# VCCS_Unit.net
KiCad netlist of a schematic drawn in EAGLE
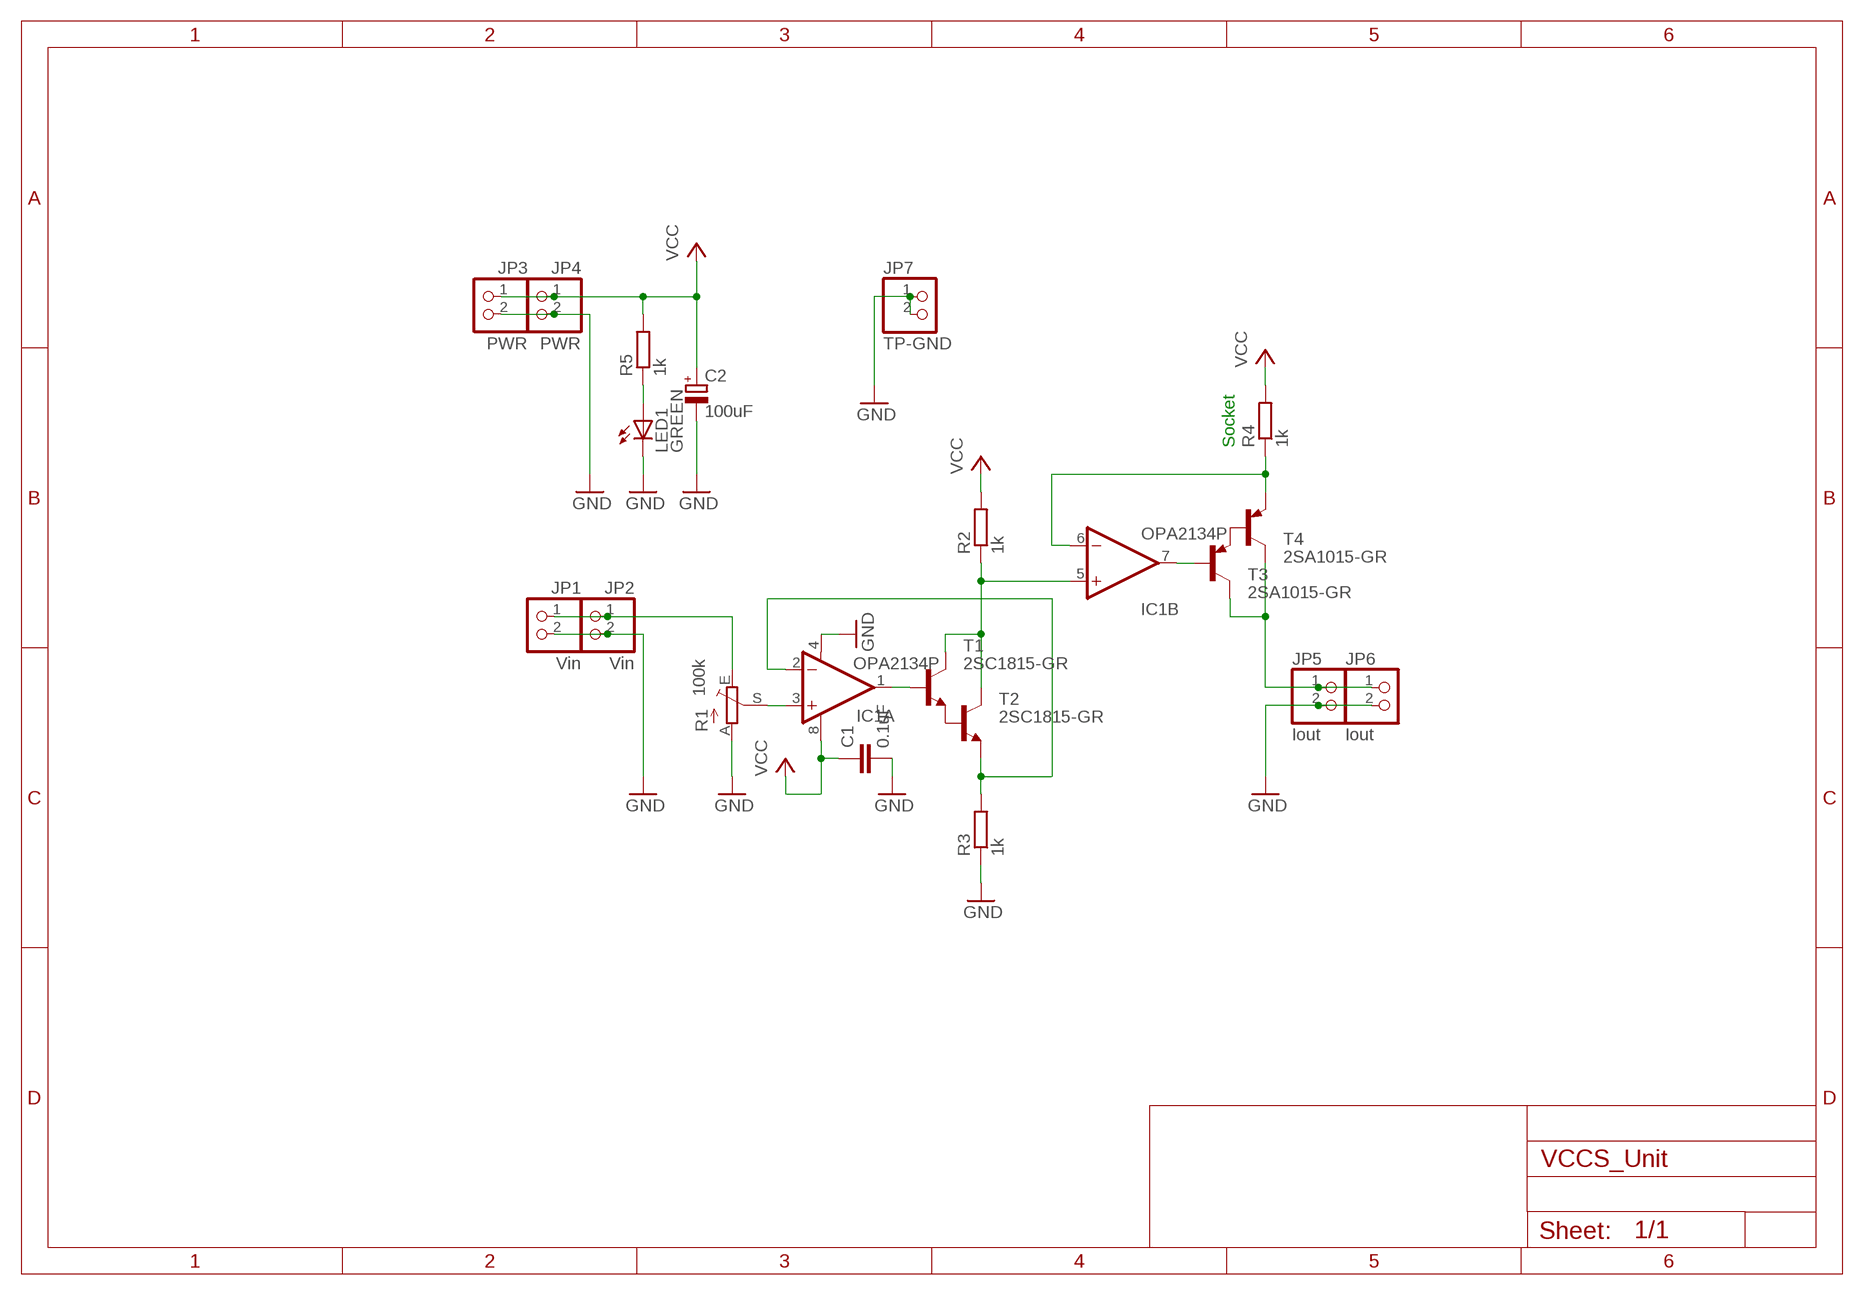
[diagram p0: schematic, sheet 1]

(export (version "E")
  (design (tool "Eeschema 10.0.6"))
  (components
    (comp (ref "C1")
      (value "0.1uF")
      (footprint "eagle-import:C025-024X044")
      (libsource (lib "eagle-import") (part "C-EU025-024X044"))
    )
    (comp (ref "C2")
      (value "100uF")
      (footprint "eagle-import:E2,5-7")
      (libsource (lib "eagle-import") (part "CPOL-EUE2.5-7"))
    )
    (comp (ref "IC1")
      (value "OPA2134P")
      (footprint "eagle-import:DIL08")
      (fields (field (name "MF") "TEXAS INSTRUMENTS") (field (name "MPN") "OPA2134PA"))
      (libsource (lib "eagle-import") (part "OPA2134P"))
    )
    (comp (ref "JP1")
      (value "Vin")
      (footprint "eagle-import:1X02")
      (libsource (lib "eagle-import") (part "PINHD-1X2"))
    )
    (comp (ref "JP2")
      (value "Vin")
      (footprint "eagle-import:1X02")
      (libsource (lib "eagle-import") (part "PINHD-1X2"))
    )
    (comp (ref "JP3")
      (value "PWR")
      (footprint "eagle-import:1X02")
      (libsource (lib "eagle-import") (part "PINHD-1X2"))
    )
    (comp (ref "JP4")
      (value "PWR")
      (footprint "eagle-import:1X02")
      (libsource (lib "eagle-import") (part "PINHD-1X2"))
    )
    (comp (ref "JP5")
      (value "Iout")
      (footprint "eagle-import:1X02")
      (libsource (lib "eagle-import") (part "PINHD-1X2"))
    )
    (comp (ref "JP6")
      (value "Iout")
      (footprint "eagle-import:1X02")
      (libsource (lib "eagle-import") (part "PINHD-1X2"))
    )
    (comp (ref "JP7")
      (value "TP-GND")
      (footprint "eagle-import:1X02")
      (libsource (lib "eagle-import") (part "PINHD-1X2"))
    )
    (comp (ref "LED1")
      (value "GREEN")
      (footprint "eagle-import:LED3MM")
      (libsource (lib "eagle-import") (part "LED3MM"))
    )
    (comp (ref "R1")
      (value "100k")
      (footprint "eagle-import:B25P")
      (libsource (lib "eagle-import") (part "TRIM_EU-B25P"))
    )
    (comp (ref "R2")
      (value "1k")
      (footprint "eagle-import:0207_7")
      (libsource (lib "eagle-import") (part "R-EU_0207/7"))
    )
    (comp (ref "R3")
      (value "1k")
      (footprint "eagle-import:0207_7")
      (libsource (lib "eagle-import") (part "R-EU_0207/7"))
    )
    (comp (ref "R4")
      (value "1k")
      (footprint "eagle-import:0207_7")
      (libsource (lib "eagle-import") (part "R-EU_0207/7"))
    )
    (comp (ref "R5")
      (value "1k")
      (footprint "eagle-import:0207_7")
      (libsource (lib "eagle-import") (part "R-EU_0207/7"))
    )
    (comp (ref "T1")
      (value "2SC1815-GR")
      (footprint "eagle-import:TO92-ECB")
      (libsource (lib "eagle-import") (part "-NPN-TO92-ECB"))
    )
    (comp (ref "T2")
      (value "2SC1815-GR")
      (footprint "eagle-import:TO92-ECB")
      (libsource (lib "eagle-import") (part "-NPN-TO92-ECB"))
    )
    (comp (ref "T3")
      (value "2SA1015-GR")
      (footprint "eagle-import:TO92-ECB")
      (libsource (lib "eagle-import") (part "-PNP-TO92-ECB"))
    )
    (comp (ref "T4")
      (value "2SA1015-GR")
      (footprint "eagle-import:TO92-ECB")
      (libsource (lib "eagle-import") (part "-PNP-TO92-ECB"))
    )
  )
  (nets
    (net (code "1") (name "GND") (class "Default")
      (node (ref "C1") (pin "2") (pinfunction "2_2") (pintype "passive"))
      (node (ref "C2") (pin "-") (pinfunction "-_-") (pintype "passive"))
      (node (ref "IC1") (pin "4") (pinfunction "V-_4") (pintype "power_in"))
      (node (ref "JP1") (pin "2") (pinfunction "2_2") (pintype "passive"))
      (node (ref "JP2") (pin "2") (pinfunction "2_2") (pintype "passive"))
      (node (ref "JP3") (pin "2") (pinfunction "2_2") (pintype "passive"))
      (node (ref "JP4") (pin "2") (pinfunction "2_2") (pintype "passive"))
      (node (ref "JP5") (pin "2") (pinfunction "2_2") (pintype "passive"))
      (node (ref "JP6") (pin "2") (pinfunction "2_2") (pintype "passive"))
      (node (ref "JP7") (pin "1") (pinfunction "1_1") (pintype "passive"))
      (node (ref "JP7") (pin "2") (pinfunction "2_2") (pintype "passive"))
      (node (ref "LED1") (pin "K") (pinfunction "C_K") (pintype "passive"))
      (node (ref "R1") (pin "A") (pinfunction "A_A") (pintype "passive"))
      (node (ref "R3") (pin "1") (pinfunction "1_1") (pintype "passive"))
    )
    (net (code "2") (name "Net-(IC1A-+IN)") (class "Default")
      (node (ref "IC1") (pin "3") (pinfunction "+IN_3") (pintype "input"))
      (node (ref "R1") (pin "S") (pinfunction "S_S") (pintype "passive"))
    )
    (net (code "3") (name "Net-(IC1A--IN)") (class "Default")
      (node (ref "IC1") (pin "2") (pinfunction "-IN_2") (pintype "input"))
      (node (ref "R3") (pin "2") (pinfunction "2_2") (pintype "passive"))
      (node (ref "T2") (pin "E") (pinfunction "E_E") (pintype "passive"))
    )
    (net (code "4") (name "Net-(IC1A-OUT)") (class "Default")
      (node (ref "IC1") (pin "1") (pinfunction "OUT_1") (pintype "output"))
      (node (ref "T1") (pin "B") (pinfunction "B_B") (pintype "passive"))
    )
    (net (code "5") (name "Net-(IC1B-+IN)") (class "Default")
      (node (ref "IC1") (pin "5") (pinfunction "+IN_5") (pintype "input"))
      (node (ref "R2") (pin "1") (pinfunction "1_1") (pintype "passive"))
      (node (ref "T1") (pin "C") (pinfunction "C_C") (pintype "passive"))
      (node (ref "T2") (pin "C") (pinfunction "C_C") (pintype "passive"))
    )
    (net (code "6") (name "Net-(IC1B--IN)") (class "Default")
      (node (ref "IC1") (pin "6") (pinfunction "-IN_6") (pintype "input"))
      (node (ref "R4") (pin "1") (pinfunction "1_1") (pintype "passive"))
      (node (ref "T4") (pin "E") (pinfunction "E_E") (pintype "passive"))
    )
    (net (code "7") (name "Net-(IC1B-OUT)") (class "Default")
      (node (ref "IC1") (pin "7") (pinfunction "OUT_7") (pintype "output"))
      (node (ref "T3") (pin "B") (pinfunction "B_B") (pintype "passive"))
    )
    (net (code "8") (name "Net-(JP1-Pad1)") (class "Default")
      (node (ref "JP1") (pin "1") (pinfunction "1_1") (pintype "passive"))
      (node (ref "JP2") (pin "1") (pinfunction "1_1") (pintype "passive"))
      (node (ref "R1") (pin "E") (pinfunction "E_E") (pintype "passive"))
    )
    (net (code "9") (name "Net-(JP5-Pad1)") (class "Default")
      (node (ref "JP5") (pin "1") (pinfunction "1_1") (pintype "passive"))
      (node (ref "JP6") (pin "1") (pinfunction "1_1") (pintype "passive"))
      (node (ref "T3") (pin "C") (pinfunction "C_C") (pintype "passive"))
      (node (ref "T4") (pin "C") (pinfunction "C_C") (pintype "passive"))
    )
    (net (code "10") (name "Net-(LED1-PadA)") (class "Default")
      (node (ref "LED1") (pin "A") (pinfunction "A_A") (pintype "passive"))
      (node (ref "R5") (pin "1") (pinfunction "1_1") (pintype "passive"))
    )
    (net (code "11") (name "Net-(T1-PadE)") (class "Default")
      (node (ref "T1") (pin "E") (pinfunction "E_E") (pintype "passive"))
      (node (ref "T2") (pin "B") (pinfunction "B_B") (pintype "passive"))
    )
    (net (code "12") (name "Net-(T3-PadE)") (class "Default")
      (node (ref "T3") (pin "E") (pinfunction "E_E") (pintype "passive"))
      (node (ref "T4") (pin "B") (pinfunction "B_B") (pintype "passive"))
    )
    (net (code "13") (name "VCC") (class "Default")
      (node (ref "C1") (pin "1") (pinfunction "1_1") (pintype "passive"))
      (node (ref "C2") (pin "+") (pinfunction "+_+") (pintype "passive"))
      (node (ref "IC1") (pin "8") (pinfunction "V+_8") (pintype "power_in"))
      (node (ref "JP3") (pin "1") (pinfunction "1_1") (pintype "passive"))
      (node (ref "JP4") (pin "1") (pinfunction "1_1") (pintype "passive"))
      (node (ref "R2") (pin "2") (pinfunction "2_2") (pintype "passive"))
      (node (ref "R4") (pin "2") (pinfunction "2_2") (pintype "passive"))
      (node (ref "R5") (pin "2") (pinfunction "2_2") (pintype "passive"))
    )
  )
)
